# TiltyDuo.net
KiCad netlist of a schematic drawn in EAGLE
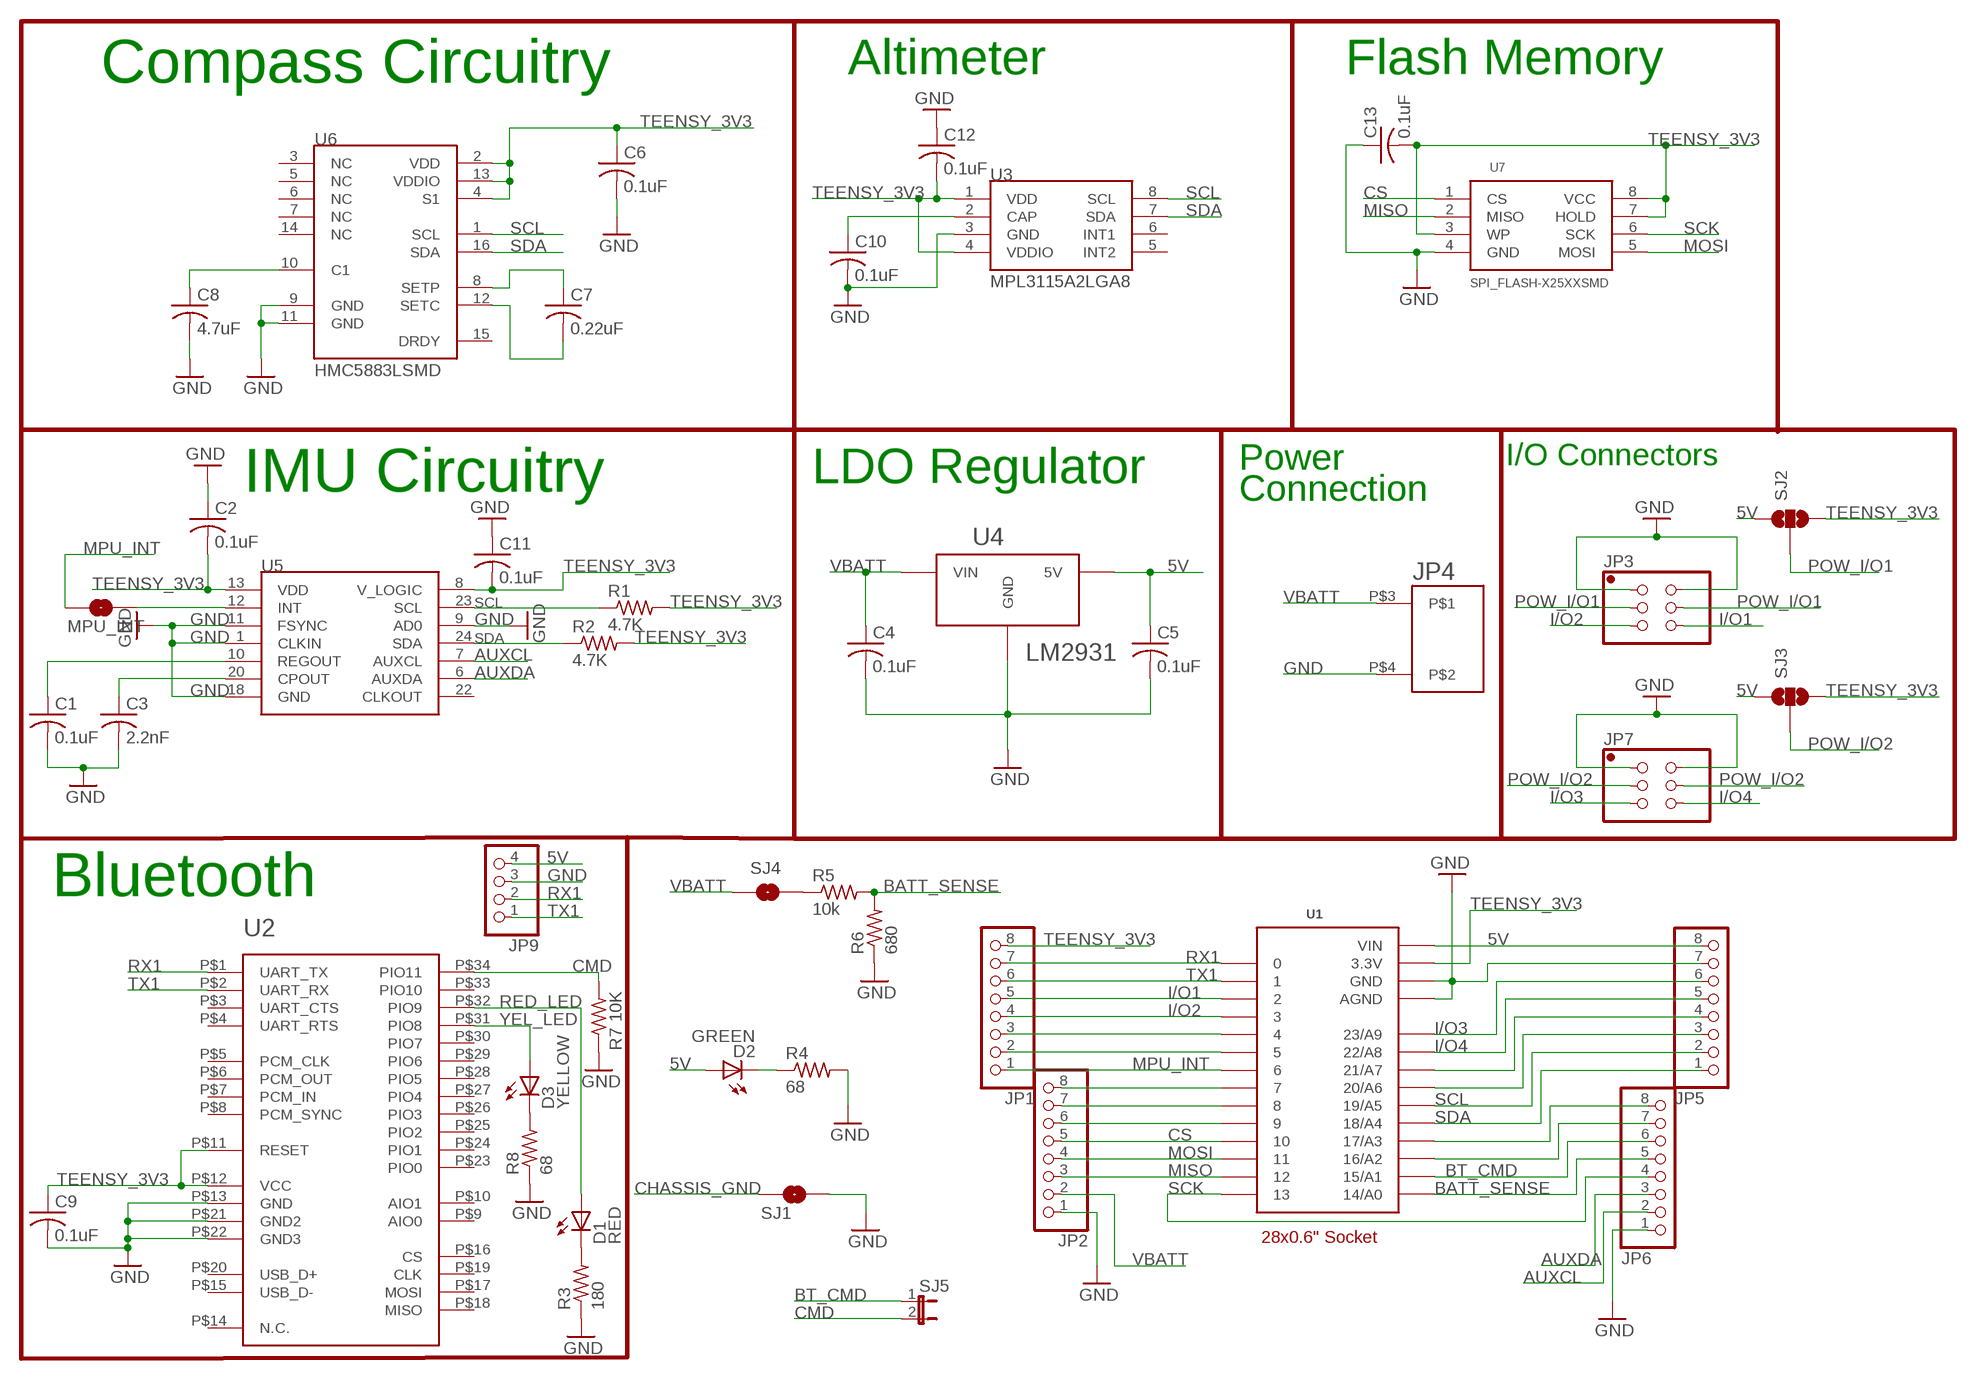
[diagram p0: schematic, sheet 1]

(export (version "E")
  (design (tool "Eeschema 10.0.6"))
  (components
    (comp (ref "C1")
      (value "0.1uF")
      (footprint "eagle-import:C0603")
      (libsource (lib "eagle-import") (part "C-USC0603"))
    )
    (comp (ref "C2")
      (value "0.1uF")
      (footprint "eagle-import:C0603")
      (libsource (lib "eagle-import") (part "C-USC0603"))
    )
    (comp (ref "C3")
      (value "2.2nF")
      (footprint "eagle-import:C0603")
      (libsource (lib "eagle-import") (part "C-USC0603"))
    )
    (comp (ref "C4")
      (value "0.1uF")
      (footprint "eagle-import:C0603")
      (libsource (lib "eagle-import") (part "C-USC0603"))
    )
    (comp (ref "C5")
      (value "0.1uF")
      (footprint "eagle-import:C0603")
      (libsource (lib "eagle-import") (part "C-USC0603"))
    )
    (comp (ref "C6")
      (value "0.1uF")
      (footprint "eagle-import:C0603")
      (libsource (lib "eagle-import") (part "C-USC0603"))
    )
    (comp (ref "C7")
      (value "0.22uF")
      (footprint "eagle-import:C0603")
      (libsource (lib "eagle-import") (part "C-USC0603"))
    )
    (comp (ref "C8")
      (value "4.7uF")
      (footprint "eagle-import:C0603")
      (libsource (lib "eagle-import") (part "C-USC0603"))
    )
    (comp (ref "C9")
      (value "0.1uF")
      (footprint "eagle-import:C0603")
      (libsource (lib "eagle-import") (part "C-USC0603"))
    )
    (comp (ref "C10")
      (value "0.1uF")
      (footprint "eagle-import:C0603")
      (libsource (lib "eagle-import") (part "C-USC0603"))
    )
    (comp (ref "C11")
      (value "0.1uF")
      (footprint "eagle-import:C0603")
      (libsource (lib "eagle-import") (part "C-USC0603"))
    )
    (comp (ref "C12")
      (value "0.1uF")
      (footprint "eagle-import:C0603")
      (libsource (lib "eagle-import") (part "C-USC0603"))
    )
    (comp (ref "C13")
      (value "0.1uF")
      (footprint "eagle-import:C0603")
      (libsource (lib "eagle-import") (part "C-USC0603"))
    )
    (comp (ref "D1")
      (value "RED")
      (footprint "eagle-import:LED-0805")
      (libsource (lib "eagle-import") (part "LED-GREENLED-0805_NO_SILK"))
    )
    (comp (ref "D2")
      (value "GREEN")
      (footprint "eagle-import:LED-0805")
      (libsource (lib "eagle-import") (part "LED-GREENLED-0805_NO_SILK"))
    )
    (comp (ref "D3")
      (value "YELLOW")
      (footprint "eagle-import:LED-0805")
      (libsource (lib "eagle-import") (part "LED-GREENLED-0805_NO_SILK"))
    )
    (comp (ref "JP1")
      (value "PINHD-1X81X08_NO_SILK_LOCK")
      (footprint "eagle-import:1X08_NO_SS_LOCKING")
      (libsource (lib "eagle-import") (part "PINHD-1X81X08_NO_SILK_LOCK"))
    )
    (comp (ref "JP2")
      (value "PINHD-1X81X08_NO_SILK_LOCK")
      (footprint "eagle-import:1X08_NO_SS_LOCKING")
      (libsource (lib "eagle-import") (part "PINHD-1X81X08_NO_SILK_LOCK"))
    )
    (comp (ref "JP3")
      (value "PINHD-2X32X03_NO_SS_LOCK")
      (footprint "eagle-import:2X03_NO_SS_LOCK")
      (libsource (lib "eagle-import") (part "PINHD-2X32X03_NO_SS_LOCK"))
    )
    (comp (ref "JP4")
      (value "2-POS_SMD_TERM_BLOCK")
      (footprint "eagle-import:2-POS_SMD_TERMINAL_BLOCK")
      (fields (field (name "PART#") "277-2337-1-ND"))
      (libsource (lib "eagle-import") (part "2-POS_SMD_TERM_BLOCK"))
    )
    (comp (ref "JP5")
      (value "PINHD-1X81X08_NO_SILK_LOCK")
      (footprint "eagle-import:1X08_NO_SS_LOCKING")
      (libsource (lib "eagle-import") (part "PINHD-1X81X08_NO_SILK_LOCK"))
    )
    (comp (ref "JP6")
      (value "PINHD-1X81X08_NO_SILK_LOCK")
      (footprint "eagle-import:1X08_NO_SS_LOCKING")
      (libsource (lib "eagle-import") (part "PINHD-1X81X08_NO_SILK_LOCK"))
    )
    (comp (ref "JP7")
      (value "PINHD-2X32X03_NO_SS_LOCK")
      (footprint "eagle-import:2X03_NO_SS_LOCK")
      (libsource (lib "eagle-import") (part "PINHD-2X32X03_NO_SS_LOCK"))
    )
    (comp (ref "JP9")
      (value "PINHD-1X41X04_NO_SS_LOCKING")
      (footprint "eagle-import:1X04_NO_SS_LOCKING")
      (libsource (lib "eagle-import") (part "PINHD-1X41X04_NO_SS_LOCKING"))
    )
    (comp (ref "MPU_INT")
      (value "SOLDERJUMPERNO")
      (footprint "eagle-import:SJ_2S-NO")
      (libsource (lib "eagle-import") (part "SOLDERJUMPERNO"))
    )
    (comp (ref "R1")
      (value "4.7K")
      (footprint "eagle-import:R0603")
      (libsource (lib "eagle-import") (part "R-US_R0603"))
    )
    (comp (ref "R2")
      (value "4.7K")
      (footprint "eagle-import:R0603")
      (libsource (lib "eagle-import") (part "R-US_R0603"))
    )
    (comp (ref "R3")
      (value "180")
      (footprint "eagle-import:R0603")
      (libsource (lib "eagle-import") (part "R-US_R0603"))
    )
    (comp (ref "R4")
      (value "68")
      (footprint "eagle-import:R0603")
      (libsource (lib "eagle-import") (part "R-US_R0603"))
    )
    (comp (ref "R5")
      (value "10k")
      (footprint "eagle-import:R0603")
      (libsource (lib "eagle-import") (part "R-US_R0603"))
    )
    (comp (ref "R6")
      (value "680")
      (footprint "eagle-import:R0603")
      (libsource (lib "eagle-import") (part "R-US_R0603"))
    )
    (comp (ref "R7")
      (value "10K")
      (footprint "eagle-import:R0603")
      (libsource (lib "eagle-import") (part "R-US_R0603"))
    )
    (comp (ref "R8")
      (value "68")
      (footprint "eagle-import:R0603")
      (libsource (lib "eagle-import") (part "R-US_R0603"))
    )
    (comp (ref "SJ1")
      (value "SOLDERJUMPERNO")
      (footprint "eagle-import:SJ_2S-NO")
      (libsource (lib "eagle-import") (part "SOLDERJUMPERNO"))
    )
    (comp (ref "SJ2")
      (value "SOLDERJUMPER_2WAYS")
      (footprint "eagle-import:SJ_3")
      (libsource (lib "eagle-import") (part "SOLDERJUMPER_2WAYS"))
    )
    (comp (ref "SJ3")
      (value "SOLDERJUMPER_2WAYS")
      (footprint "eagle-import:SJ_3")
      (libsource (lib "eagle-import") (part "SOLDERJUMPER_2WAYS"))
    )
    (comp (ref "SJ4")
      (value "SOLDERJUMPERTRACE")
      (footprint "eagle-import:SJ_2S-TRACE")
      (libsource (lib "eagle-import") (part "SOLDERJUMPERTRACE"))
    )
    (comp (ref "SJ5")
      (value "JUMPER-2SMD-NC")
      (footprint "eagle-import:SJ_2S")
      (libsource (lib "eagle-import") (part "JUMPER-2SMD-NC"))
    )
    (comp (ref "U1")
      (value "TEENSY_3.0_OUTER-PINS28-DIP_SOCKET")
      (footprint "eagle-import:28-DIP")
      (fields (field (name "PART#") "AE10004-ND"))
      (libsource (lib "eagle-import") (part "TEENSY_3.0_OUTER-PINS28-DIP_SOCKET"))
    )
    (comp (ref "U2")
      (value "HC-09_BREAKOUT")
      (footprint "eagle-import:HC-09_BREAKOUT")
      (libsource (lib "eagle-import") (part "HC-09_BREAKOUT"))
    )
    (comp (ref "U3")
      (value "MPL3115A2LGA8")
      (footprint "eagle-import:LGA8")
      (libsource (lib "eagle-import") (part "MPL3115A2LGA8"))
    )
    (comp (ref "U4")
      (value "LM2931")
      (footprint "eagle-import:TO263")
      (libsource (lib "eagle-import") (part "LM2931"))
    )
    (comp (ref "U5")
      (value "MPU-6050")
      (footprint "eagle-import:QFN-24")
      (libsource (lib "eagle-import") (part "MPU-6050"))
    )
    (comp (ref "U6")
      (value "HMC5883LSMD")
      (footprint "eagle-import:16LPCC")
      (libsource (lib "eagle-import") (part "HMC5883LSMD"))
    )
    (comp (ref "U7")
      (value "SPI_FLASH-X25XXSMD")
      (footprint "eagle-import:SO08")
      (fields (field (name "PART#") "S25FL204K0TMFI043"))
      (libsource (lib "eagle-import") (part "SPI_FLASH-X25XXSMD"))
    )
  )
  (nets
    (net (code "1") (name "/5V") (class "Default")
      (node (ref "C5") (pin "1") (pinfunction "1_1") (pintype "passive"))
      (node (ref "D2") (pin "1") (pinfunction "A_1") (pintype "passive"))
      (node (ref "JP5") (pin "8") (pinfunction "8_8") (pintype "passive"))
      (node (ref "JP9") (pin "4") (pinfunction "4_4") (pintype "passive"))
      (node (ref "SJ2") (pin "1") (pinfunction "1_1") (pintype "passive"))
      (node (ref "SJ3") (pin "1") (pinfunction "1_1") (pintype "passive"))
      (node (ref "U1") (pin "P$15") (pinfunction "VIN_P$15") (pintype "power_in"))
      (node (ref "U4") (pin "P$3") (pinfunction "5V_P$3") (pintype "bidirectional"))
    )
    (net (code "2") (name "/AUXCL") (class "Default")
      (node (ref "JP6") (pin "2") (pinfunction "2_2") (pintype "passive"))
      (node (ref "U5") (pin "7") (pinfunction "AUXCL_7") (pintype "bidirectional"))
    )
    (net (code "3") (name "/AUXDA") (class "Default")
      (node (ref "JP6") (pin "3") (pinfunction "3_3") (pintype "passive"))
      (node (ref "U5") (pin "6") (pinfunction "AUXDA_6") (pintype "bidirectional"))
    )
    (net (code "4") (name "/BATT_SENSE") (class "Default")
      (node (ref "JP6") (pin "5") (pinfunction "5_5") (pintype "passive"))
      (node (ref "R5") (pin "2") (pinfunction "2_2") (pintype "passive"))
      (node (ref "R6") (pin "2") (pinfunction "2_2") (pintype "passive"))
      (node (ref "U1") (pin "P$27") (pinfunction "14/A0_P$27") (pintype "bidirectional"))
    )
    (net (code "5") (name "/BT_CMD") (class "Default")
      (node (ref "JP6") (pin "6") (pinfunction "6_6") (pintype "passive"))
      (node (ref "SJ5") (pin "1") (pinfunction "1_1") (pintype "passive"))
      (node (ref "U1") (pin "P$26") (pinfunction "15/A1_P$26") (pintype "bidirectional"))
    )
    (net (code "6") (name "/CHASSIS_GND") (class "Default")
      (node (ref "SJ1") (pin "1") (pinfunction "1_1") (pintype "passive"))
    )
    (net (code "7") (name "/CMD") (class "Default")
      (node (ref "R7") (pin "2") (pinfunction "2_2") (pintype "passive"))
      (node (ref "SJ5") (pin "2") (pinfunction "2_2") (pintype "passive"))
      (node (ref "U2") (pin "P$34") (pinfunction "PIO11_P$34") (pintype "bidirectional"))
    )
    (net (code "8") (name "/CS") (class "Default")
      (node (ref "JP2") (pin "5") (pinfunction "5_5") (pintype "passive"))
      (node (ref "U1") (pin "P$12") (pinfunction "10_P$12") (pintype "bidirectional"))
      (node (ref "U7") (pin "1") (pinfunction "CS_1") (pintype "bidirectional"))
    )
    (net (code "9") (name "/I{slash}O1") (class "Default")
      (node (ref "JP1") (pin "5") (pinfunction "5_5") (pintype "passive"))
      (node (ref "JP3") (pin "6") (pinfunction "6_6") (pintype "passive"))
      (node (ref "U1") (pin "P$4") (pinfunction "2_P$4") (pintype "bidirectional"))
    )
    (net (code "10") (name "/I{slash}O2") (class "Default")
      (node (ref "JP1") (pin "4") (pinfunction "4_4") (pintype "passive"))
      (node (ref "JP3") (pin "5") (pinfunction "5_5") (pintype "passive"))
      (node (ref "U1") (pin "P$5") (pinfunction "3_P$5") (pintype "bidirectional"))
    )
    (net (code "11") (name "/I{slash}O3") (class "Default")
      (node (ref "JP5") (pin "6") (pinfunction "6_6") (pintype "passive"))
      (node (ref "JP7") (pin "5") (pinfunction "5_5") (pintype "passive"))
      (node (ref "U1") (pin "P$18") (pinfunction "23/A9_P$18") (pintype "bidirectional"))
    )
    (net (code "12") (name "/I{slash}O4") (class "Default")
      (node (ref "JP5") (pin "5") (pinfunction "5_5") (pintype "passive"))
      (node (ref "JP7") (pin "6") (pinfunction "6_6") (pintype "passive"))
      (node (ref "U1") (pin "P$19") (pinfunction "22/A8_P$19") (pintype "bidirectional"))
    )
    (net (code "13") (name "/MISO") (class "Default")
      (node (ref "JP2") (pin "3") (pinfunction "3_3") (pintype "passive"))
      (node (ref "U1") (pin "P$14") (pinfunction "12_P$14") (pintype "bidirectional"))
      (node (ref "U7") (pin "2") (pinfunction "MISO_2") (pintype "bidirectional"))
    )
    (net (code "14") (name "/MOSI") (class "Default")
      (node (ref "JP2") (pin "4") (pinfunction "4_4") (pintype "passive"))
      (node (ref "U1") (pin "P$13") (pinfunction "11_P$13") (pintype "bidirectional"))
      (node (ref "U7") (pin "5") (pinfunction "MOSI_5") (pintype "bidirectional"))
    )
    (net (code "15") (name "/MPU_INT") (class "Default")
      (node (ref "JP1") (pin "1") (pinfunction "1_1") (pintype "passive"))
      (node (ref "MPU_INT") (pin "1") (pinfunction "1_1") (pintype "passive"))
      (node (ref "U1") (pin "P$8") (pinfunction "6_P$8") (pintype "bidirectional"))
    )
    (net (code "16") (name "/POW_I{slash}O1") (class "Default")
      (node (ref "JP3") (pin "3") (pinfunction "3_3") (pintype "passive"))
      (node (ref "JP3") (pin "4") (pinfunction "4_4") (pintype "passive"))
      (node (ref "SJ2") (pin "2") (pinfunction "2_2") (pintype "passive"))
    )
    (net (code "17") (name "/POW_I{slash}O2") (class "Default")
      (node (ref "JP7") (pin "3") (pinfunction "3_3") (pintype "passive"))
      (node (ref "JP7") (pin "4") (pinfunction "4_4") (pintype "passive"))
      (node (ref "SJ3") (pin "2") (pinfunction "2_2") (pintype "passive"))
    )
    (net (code "18") (name "/RED_LED") (class "Default")
      (node (ref "D1") (pin "1") (pinfunction "A_1") (pintype "passive"))
      (node (ref "U2") (pin "P$32") (pinfunction "PIO9_P$32") (pintype "bidirectional"))
    )
    (net (code "19") (name "/RX1") (class "Default")
      (node (ref "JP1") (pin "7") (pinfunction "7_7") (pintype "passive"))
      (node (ref "JP9") (pin "2") (pinfunction "2_2") (pintype "passive"))
      (node (ref "U1") (pin "P$2") (pinfunction "0_P$2") (pintype "bidirectional"))
      (node (ref "U2") (pin "P$1") (pinfunction "UART_TX_P$1") (pintype "bidirectional"))
    )
    (net (code "20") (name "/SCK") (class "Default")
      (node (ref "JP6") (pin "4") (pinfunction "4_4") (pintype "passive"))
      (node (ref "U1") (pin "P$28") (pinfunction "13_P$28") (pintype "bidirectional"))
      (node (ref "U7") (pin "6") (pinfunction "SCK_6") (pintype "bidirectional"))
    )
    (net (code "21") (name "/SCL") (class "Default")
      (node (ref "JP5") (pin "2") (pinfunction "2_2") (pintype "passive"))
      (node (ref "R1") (pin "1") (pinfunction "1_1") (pintype "passive"))
      (node (ref "U1") (pin "P$22") (pinfunction "19/A5_P$22") (pintype "bidirectional"))
      (node (ref "U3") (pin "8") (pinfunction "SCL_8") (pintype "bidirectional"))
      (node (ref "U5") (pin "23") (pinfunction "SCL_23") (pintype "bidirectional"))
      (node (ref "U6") (pin "1") (pinfunction "SCL_1") (pintype "bidirectional"))
    )
    (net (code "22") (name "/SDA") (class "Default")
      (node (ref "JP5") (pin "1") (pinfunction "1_1") (pintype "passive"))
      (node (ref "R2") (pin "1") (pinfunction "1_1") (pintype "passive"))
      (node (ref "U1") (pin "P$23") (pinfunction "18/A4_P$23") (pintype "bidirectional"))
      (node (ref "U3") (pin "7") (pinfunction "SDA_7") (pintype "bidirectional"))
      (node (ref "U5") (pin "24") (pinfunction "SDA_24") (pintype "bidirectional"))
      (node (ref "U6") (pin "16") (pinfunction "SDA_16") (pintype "bidirectional"))
    )
    (net (code "23") (name "/TEENSY_3V3") (class "Default")
      (node (ref "C11") (pin "2") (pinfunction "2_2") (pintype "passive"))
      (node (ref "C12") (pin "2") (pinfunction "2_2") (pintype "passive"))
      (node (ref "C13") (pin "2") (pinfunction "2_2") (pintype "passive"))
      (node (ref "C2") (pin "2") (pinfunction "2_2") (pintype "passive"))
      (node (ref "C6") (pin "1") (pinfunction "1_1") (pintype "passive"))
      (node (ref "C9") (pin "1") (pinfunction "1_1") (pintype "passive"))
      (node (ref "JP1") (pin "8") (pinfunction "8_8") (pintype "passive"))
      (node (ref "R1") (pin "2") (pinfunction "2_2") (pintype "passive"))
      (node (ref "R2") (pin "2") (pinfunction "2_2") (pintype "passive"))
      (node (ref "SJ2") (pin "3") (pinfunction "3_3") (pintype "passive"))
      (node (ref "SJ3") (pin "3") (pinfunction "3_3") (pintype "passive"))
      (node (ref "U1") (pin "P$17") (pinfunction "3.3V_P$17") (pintype "power_in"))
      (node (ref "U2") (pin "P$11") (pinfunction "RESET_P$11") (pintype "bidirectional"))
      (node (ref "U2") (pin "P$12") (pinfunction "VCC_P$12") (pintype "bidirectional"))
      (node (ref "U3") (pin "1") (pinfunction "VDD_1") (pintype "bidirectional"))
      (node (ref "U3") (pin "4") (pinfunction "VDDIO_4") (pintype "bidirectional"))
      (node (ref "U5") (pin "13") (pinfunction "VDD_13") (pintype "bidirectional"))
      (node (ref "U5") (pin "8") (pinfunction "V_LOGIC_8") (pintype "bidirectional"))
      (node (ref "U6") (pin "13") (pinfunction "VDDIO_13") (pintype "bidirectional"))
      (node (ref "U6") (pin "2") (pinfunction "VDD_2") (pintype "bidirectional"))
      (node (ref "U6") (pin "4") (pinfunction "S1_4") (pintype "bidirectional"))
      (node (ref "U7") (pin "3") (pinfunction "WP_3") (pintype "bidirectional"))
      (node (ref "U7") (pin "7") (pinfunction "HOLD_7") (pintype "bidirectional"))
      (node (ref "U7") (pin "8") (pinfunction "VCC_8") (pintype "bidirectional"))
    )
    (net (code "24") (name "/TX1") (class "Default")
      (node (ref "JP1") (pin "6") (pinfunction "6_6") (pintype "passive"))
      (node (ref "JP9") (pin "1") (pinfunction "1_1") (pintype "passive"))
      (node (ref "U1") (pin "P$3") (pinfunction "1_P$3") (pintype "bidirectional"))
      (node (ref "U2") (pin "P$2") (pinfunction "UART_RX_P$2") (pintype "bidirectional"))
    )
    (net (code "25") (name "/VBATT") (class "Default")
      (node (ref "C4") (pin "1") (pinfunction "1_1") (pintype "passive"))
      (node (ref "JP2") (pin "2") (pinfunction "2_2") (pintype "passive"))
      (node (ref "JP4") (pin "P$3") (pinfunction "P$1_P$3") (pintype "bidirectional"))
      (node (ref "SJ4") (pin "1") (pinfunction "1_1") (pintype "passive"))
      (node (ref "U4") (pin "P$2") (pinfunction "VIN_P$2") (pintype "bidirectional"))
    )
    (net (code "26") (name "/YEL_LED") (class "Default")
      (node (ref "D3") (pin "1") (pinfunction "A_1") (pintype "passive"))
      (node (ref "U2") (pin "P$31") (pinfunction "PIO8_P$31") (pintype "bidirectional"))
    )
    (net (code "27") (name "GND") (class "Default")
      (node (ref "C1") (pin "2") (pinfunction "2_2") (pintype "passive"))
      (node (ref "C10") (pin "2") (pinfunction "2_2") (pintype "passive"))
      (node (ref "C11") (pin "1") (pinfunction "1_1") (pintype "passive"))
      (node (ref "C12") (pin "1") (pinfunction "1_1") (pintype "passive"))
      (node (ref "C13") (pin "1") (pinfunction "1_1") (pintype "passive"))
      (node (ref "C2") (pin "1") (pinfunction "1_1") (pintype "passive"))
      (node (ref "C3") (pin "2") (pinfunction "2_2") (pintype "passive"))
      (node (ref "C4") (pin "2") (pinfunction "2_2") (pintype "passive"))
      (node (ref "C5") (pin "2") (pinfunction "2_2") (pintype "passive"))
      (node (ref "C6") (pin "2") (pinfunction "2_2") (pintype "passive"))
      (node (ref "C8") (pin "2") (pinfunction "2_2") (pintype "passive"))
      (node (ref "C9") (pin "2") (pinfunction "2_2") (pintype "passive"))
      (node (ref "JP2") (pin "1") (pinfunction "1_1") (pintype "passive"))
      (node (ref "JP3") (pin "1") (pinfunction "1_1") (pintype "passive"))
      (node (ref "JP3") (pin "2") (pinfunction "2_2") (pintype "passive"))
      (node (ref "JP4") (pin "P$4") (pinfunction "P$2_P$4") (pintype "bidirectional"))
      (node (ref "JP5") (pin "7") (pinfunction "7_7") (pintype "passive"))
      (node (ref "JP6") (pin "1") (pinfunction "1_1") (pintype "passive"))
      (node (ref "JP7") (pin "1") (pinfunction "1_1") (pintype "passive"))
      (node (ref "JP7") (pin "2") (pinfunction "2_2") (pintype "passive"))
      (node (ref "JP9") (pin "3") (pinfunction "3_3") (pintype "passive"))
      (node (ref "R3") (pin "1") (pinfunction "1_1") (pintype "passive"))
      (node (ref "R4") (pin "2") (pinfunction "2_2") (pintype "passive"))
      (node (ref "R6") (pin "1") (pinfunction "1_1") (pintype "passive"))
      (node (ref "R7") (pin "1") (pinfunction "1_1") (pintype "passive"))
      (node (ref "R8") (pin "1") (pinfunction "1_1") (pintype "passive"))
      (node (ref "SJ1") (pin "2") (pinfunction "2_2") (pintype "passive"))
      (node (ref "U1") (pin "P$1") (pinfunction "GND_P$1") (pintype "power_in"))
      (node (ref "U1") (pin "P$16") (pinfunction "AGND_P$16") (pintype "power_in"))
      (node (ref "U2") (pin "P$13") (pinfunction "GND_P$13") (pintype "bidirectional"))
      (node (ref "U2") (pin "P$21") (pinfunction "GND2_P$21") (pintype "bidirectional"))
      (node (ref "U2") (pin "P$22") (pinfunction "GND3_P$22") (pintype "bidirectional"))
      (node (ref "U3") (pin "3") (pinfunction "GND_3") (pintype "bidirectional"))
      (node (ref "U4") (pin "P$1") (pinfunction "GND_P$1") (pintype "bidirectional"))
      (node (ref "U5") (pin "1") (pinfunction "CLKIN_1") (pintype "bidirectional"))
      (node (ref "U5") (pin "11") (pinfunction "FSYNC_11") (pintype "bidirectional"))
      (node (ref "U5") (pin "18") (pinfunction "GND_18") (pintype "bidirectional"))
      (node (ref "U5") (pin "9") (pinfunction "AD0_9") (pintype "bidirectional"))
      (node (ref "U6") (pin "11") (pinfunction "GND_11") (pintype "bidirectional"))
      (node (ref "U6") (pin "9") (pinfunction "GND_9") (pintype "bidirectional"))
      (node (ref "U7") (pin "4") (pinfunction "GND_4") (pintype "bidirectional"))
    )
    (net (code "28") (name "Net-(D1-C)") (class "Default")
      (node (ref "D1") (pin "2") (pinfunction "C_2") (pintype "passive"))
      (node (ref "R3") (pin "2") (pinfunction "2_2") (pintype "passive"))
    )
    (net (code "29") (name "Net-(D2-C)") (class "Default")
      (node (ref "D2") (pin "2") (pinfunction "C_2") (pintype "passive"))
      (node (ref "R4") (pin "1") (pinfunction "1_1") (pintype "passive"))
    )
    (net (code "30") (name "Net-(D3-C)") (class "Default")
      (node (ref "D3") (pin "2") (pinfunction "C_2") (pintype "passive"))
      (node (ref "R8") (pin "2") (pinfunction "2_2") (pintype "passive"))
    )
    (net (code "31") (name "Net-(R5-Pad1)") (class "Default")
      (node (ref "R5") (pin "1") (pinfunction "1_1") (pintype "passive"))
      (node (ref "SJ4") (pin "2") (pinfunction "2_2") (pintype "passive"))
    )
    (net (code "32") (name "Net-(U1-4)") (class "Default")
      (node (ref "JP1") (pin "3") (pinfunction "3_3") (pintype "passive"))
      (node (ref "U1") (pin "P$6") (pinfunction "4_P$6") (pintype "bidirectional"))
    )
    (net (code "33") (name "Net-(U1-5)") (class "Default")
      (node (ref "JP1") (pin "2") (pinfunction "2_2") (pintype "passive"))
      (node (ref "U1") (pin "P$7") (pinfunction "5_P$7") (pintype "bidirectional"))
    )
    (net (code "34") (name "Net-(U1-7)") (class "Default")
      (node (ref "JP2") (pin "8") (pinfunction "8_8") (pintype "passive"))
      (node (ref "U1") (pin "P$9") (pinfunction "7_P$9") (pintype "bidirectional"))
    )
    (net (code "35") (name "Net-(U1-8)") (class "Default")
      (node (ref "JP2") (pin "7") (pinfunction "7_7") (pintype "passive"))
      (node (ref "U1") (pin "P$10") (pinfunction "8_P$10") (pintype "bidirectional"))
    )
    (net (code "36") (name "Net-(U1-9)") (class "Default")
      (node (ref "JP2") (pin "6") (pinfunction "6_6") (pintype "passive"))
      (node (ref "U1") (pin "P$11") (pinfunction "9_P$11") (pintype "bidirectional"))
    )
    (net (code "37") (name "Net-(U1-16{slash}A2)") (class "Default")
      (node (ref "JP6") (pin "7") (pinfunction "7_7") (pintype "passive"))
      (node (ref "U1") (pin "P$25") (pinfunction "16/A2_P$25") (pintype "bidirectional"))
    )
    (net (code "38") (name "Net-(U1-17{slash}A3)") (class "Default")
      (node (ref "JP6") (pin "8") (pinfunction "8_8") (pintype "passive"))
      (node (ref "U1") (pin "P$24") (pinfunction "17/A3_P$24") (pintype "bidirectional"))
    )
    (net (code "39") (name "Net-(U1-20{slash}A6)") (class "Default")
      (node (ref "JP5") (pin "3") (pinfunction "3_3") (pintype "passive"))
      (node (ref "U1") (pin "P$21") (pinfunction "20/A6_P$21") (pintype "bidirectional"))
    )
    (net (code "40") (name "Net-(U1-21{slash}A7)") (class "Default")
      (node (ref "JP5") (pin "4") (pinfunction "4_4") (pintype "passive"))
      (node (ref "U1") (pin "P$20") (pinfunction "21/A7_P$20") (pintype "bidirectional"))
    )
    (net (code "41") (name "Net-(U3-CAP)") (class "Default")
      (node (ref "C10") (pin "1") (pinfunction "1_1") (pintype "passive"))
      (node (ref "U3") (pin "2") (pinfunction "CAP_2") (pintype "bidirectional"))
    )
    (net (code "42") (name "Net-(U5-CPOUT)") (class "Default")
      (node (ref "C3") (pin "1") (pinfunction "1_1") (pintype "passive"))
      (node (ref "U5") (pin "20") (pinfunction "CPOUT_20") (pintype "bidirectional"))
    )
    (net (code "43") (name "Net-(U5-INT)") (class "Default")
      (node (ref "MPU_INT") (pin "2") (pinfunction "2_2") (pintype "passive"))
      (node (ref "U5") (pin "12") (pinfunction "INT_12") (pintype "bidirectional"))
    )
    (net (code "44") (name "Net-(U5-REGOUT)") (class "Default")
      (node (ref "C1") (pin "1") (pinfunction "1_1") (pintype "passive"))
      (node (ref "U5") (pin "10") (pinfunction "REGOUT_10") (pintype "bidirectional"))
    )
    (net (code "45") (name "Net-(U6-C1)") (class "Default")
      (node (ref "C8") (pin "1") (pinfunction "1_1") (pintype "passive"))
      (node (ref "U6") (pin "10") (pinfunction "C1_10") (pintype "bidirectional"))
    )
    (net (code "46") (name "Net-(U6-SETC)") (class "Default")
      (node (ref "C7") (pin "2") (pinfunction "2_2") (pintype "passive"))
      (node (ref "U6") (pin "12") (pinfunction "SETC_12") (pintype "bidirectional"))
    )
    (net (code "47") (name "Net-(U6-SETP)") (class "Default")
      (node (ref "C7") (pin "1") (pinfunction "1_1") (pintype "passive"))
      (node (ref "U6") (pin "8") (pinfunction "SETP_8") (pintype "bidirectional"))
    )
    (net (code "48") (name "unconnected-(U2-AIO0-PadP$9)") (class "Default")
      (node (ref "U2") (pin "P$9") (pinfunction "AIO0_P$9") (pintype "bidirectional"))
    )
    (net (code "49") (name "unconnected-(U2-AIO1-PadP$10)") (class "Default")
      (node (ref "U2") (pin "P$10") (pinfunction "AIO1_P$10") (pintype "bidirectional"))
    )
    (net (code "50") (name "unconnected-(U2-CLK-PadP$19)") (class "Default")
      (node (ref "U2") (pin "P$19") (pinfunction "CLK_P$19") (pintype "bidirectional"))
    )
    (net (code "51") (name "unconnected-(U2-CS-PadP$16)") (class "Default")
      (node (ref "U2") (pin "P$16") (pinfunction "CS_P$16") (pintype "bidirectional"))
    )
    (net (code "52") (name "unconnected-(U2-MISO-PadP$18)") (class "Default")
      (node (ref "U2") (pin "P$18") (pinfunction "MISO_P$18") (pintype "bidirectional"))
    )
    (net (code "53") (name "unconnected-(U2-MOSI-PadP$17)") (class "Default")
      (node (ref "U2") (pin "P$17") (pinfunction "MOSI_P$17") (pintype "bidirectional"))
    )
    (net (code "54") (name "unconnected-(U2-N.C.-PadP$14)") (class "Default")
      (node (ref "U2") (pin "P$14") (pinfunction "N.C._P$14") (pintype "bidirectional"))
    )
    (net (code "55") (name "unconnected-(U2-PCM_CLK-PadP$5)") (class "Default")
      (node (ref "U2") (pin "P$5") (pinfunction "PCM_CLK_P$5") (pintype "bidirectional"))
    )
    (net (code "56") (name "unconnected-(U2-PCM_IN-PadP$7)") (class "Default")
      (node (ref "U2") (pin "P$7") (pinfunction "PCM_IN_P$7") (pintype "bidirectional"))
    )
    (net (code "57") (name "unconnected-(U2-PCM_OUT-PadP$6)") (class "Default")
      (node (ref "U2") (pin "P$6") (pinfunction "PCM_OUT_P$6") (pintype "bidirectional"))
    )
    (net (code "58") (name "unconnected-(U2-PCM_SYNC-PadP$8)") (class "Default")
      (node (ref "U2") (pin "P$8") (pinfunction "PCM_SYNC_P$8") (pintype "bidirectional"))
    )
    (net (code "59") (name "unconnected-(U2-PIO0-PadP$23)") (class "Default")
      (node (ref "U2") (pin "P$23") (pinfunction "PIO0_P$23") (pintype "bidirectional"))
    )
    (net (code "60") (name "unconnected-(U2-PIO1-PadP$24)") (class "Default")
      (node (ref "U2") (pin "P$24") (pinfunction "PIO1_P$24") (pintype "bidirectional"))
    )
    (net (code "61") (name "unconnected-(U2-PIO2-PadP$25)") (class "Default")
      (node (ref "U2") (pin "P$25") (pinfunction "PIO2_P$25") (pintype "bidirectional"))
    )
    (net (code "62") (name "unconnected-(U2-PIO3-PadP$26)") (class "Default")
      (node (ref "U2") (pin "P$26") (pinfunction "PIO3_P$26") (pintype "bidirectional"))
    )
    (net (code "63") (name "unconnected-(U2-PIO4-PadP$27)") (class "Default")
      (node (ref "U2") (pin "P$27") (pinfunction "PIO4_P$27") (pintype "bidirectional"))
    )
    (net (code "64") (name "unconnected-(U2-PIO5-PadP$28)") (class "Default")
      (node (ref "U2") (pin "P$28") (pinfunction "PIO5_P$28") (pintype "bidirectional"))
    )
    (net (code "65") (name "unconnected-(U2-PIO6-PadP$29)") (class "Default")
      (node (ref "U2") (pin "P$29") (pinfunction "PIO6_P$29") (pintype "bidirectional"))
    )
    (net (code "66") (name "unconnected-(U2-PIO7-PadP$30)") (class "Default")
      (node (ref "U2") (pin "P$30") (pinfunction "PIO7_P$30") (pintype "bidirectional"))
    )
    (net (code "67") (name "unconnected-(U2-PIO10-PadP$33)") (class "Default")
      (node (ref "U2") (pin "P$33") (pinfunction "PIO10_P$33") (pintype "bidirectional"))
    )
    (net (code "68") (name "unconnected-(U2-UART_CTS-PadP$3)") (class "Default")
      (node (ref "U2") (pin "P$3") (pinfunction "UART_CTS_P$3") (pintype "bidirectional"))
    )
    (net (code "69") (name "unconnected-(U2-UART_RTS-PadP$4)") (class "Default")
      (node (ref "U2") (pin "P$4") (pinfunction "UART_RTS_P$4") (pintype "bidirectional"))
    )
    (net (code "70") (name "unconnected-(U2-USB_D+-PadP$20)") (class "Default")
      (node (ref "U2") (pin "P$20") (pinfunction "USB_D+_P$20") (pintype "bidirectional"))
    )
    (net (code "71") (name "unconnected-(U2-USB_D--PadP$15)") (class "Default")
      (node (ref "U2") (pin "P$15") (pinfunction "USB_D-_P$15") (pintype "bidirectional"))
    )
    (net (code "72") (name "unconnected-(U3-INT1-Pad6)") (class "Default")
      (node (ref "U3") (pin "6") (pinfunction "INT1_6") (pintype "bidirectional"))
    )
    (net (code "73") (name "unconnected-(U3-INT2-Pad5)") (class "Default")
      (node (ref "U3") (pin "5") (pinfunction "INT2_5") (pintype "bidirectional"))
    )
    (net (code "74") (name "unconnected-(U5-CLKOUT-Pad22)") (class "Default")
      (node (ref "U5") (pin "22") (pinfunction "CLKOUT_22") (pintype "bidirectional"))
    )
    (net (code "75") (name "unconnected-(U6-DRDY-Pad15)") (class "Default")
      (node (ref "U6") (pin "15") (pinfunction "DRDY_15") (pintype "bidirectional"))
    )
    (net (code "76") (name "unconnected-(U6-NC-Pad3)") (class "Default")
      (node (ref "U6") (pin "3") (pinfunction "NC_3") (pintype "bidirectional"))
    )
    (net (code "77") (name "unconnected-(U6-NC-Pad5)") (class "Default")
      (node (ref "U6") (pin "5") (pinfunction "NC_5") (pintype "bidirectional"))
    )
    (net (code "78") (name "unconnected-(U6-NC-Pad6)") (class "Default")
      (node (ref "U6") (pin "6") (pinfunction "NC_6") (pintype "bidirectional"))
    )
    (net (code "79") (name "unconnected-(U6-NC-Pad7)") (class "Default")
      (node (ref "U6") (pin "7") (pinfunction "NC_7") (pintype "bidirectional"))
    )
    (net (code "80") (name "unconnected-(U6-NC-Pad14)") (class "Default")
      (node (ref "U6") (pin "14") (pinfunction "NC_14") (pintype "bidirectional"))
    )
  )
)
